# Dashboard_rev1.net
KiCad netlist of a schematic drawn in EAGLE
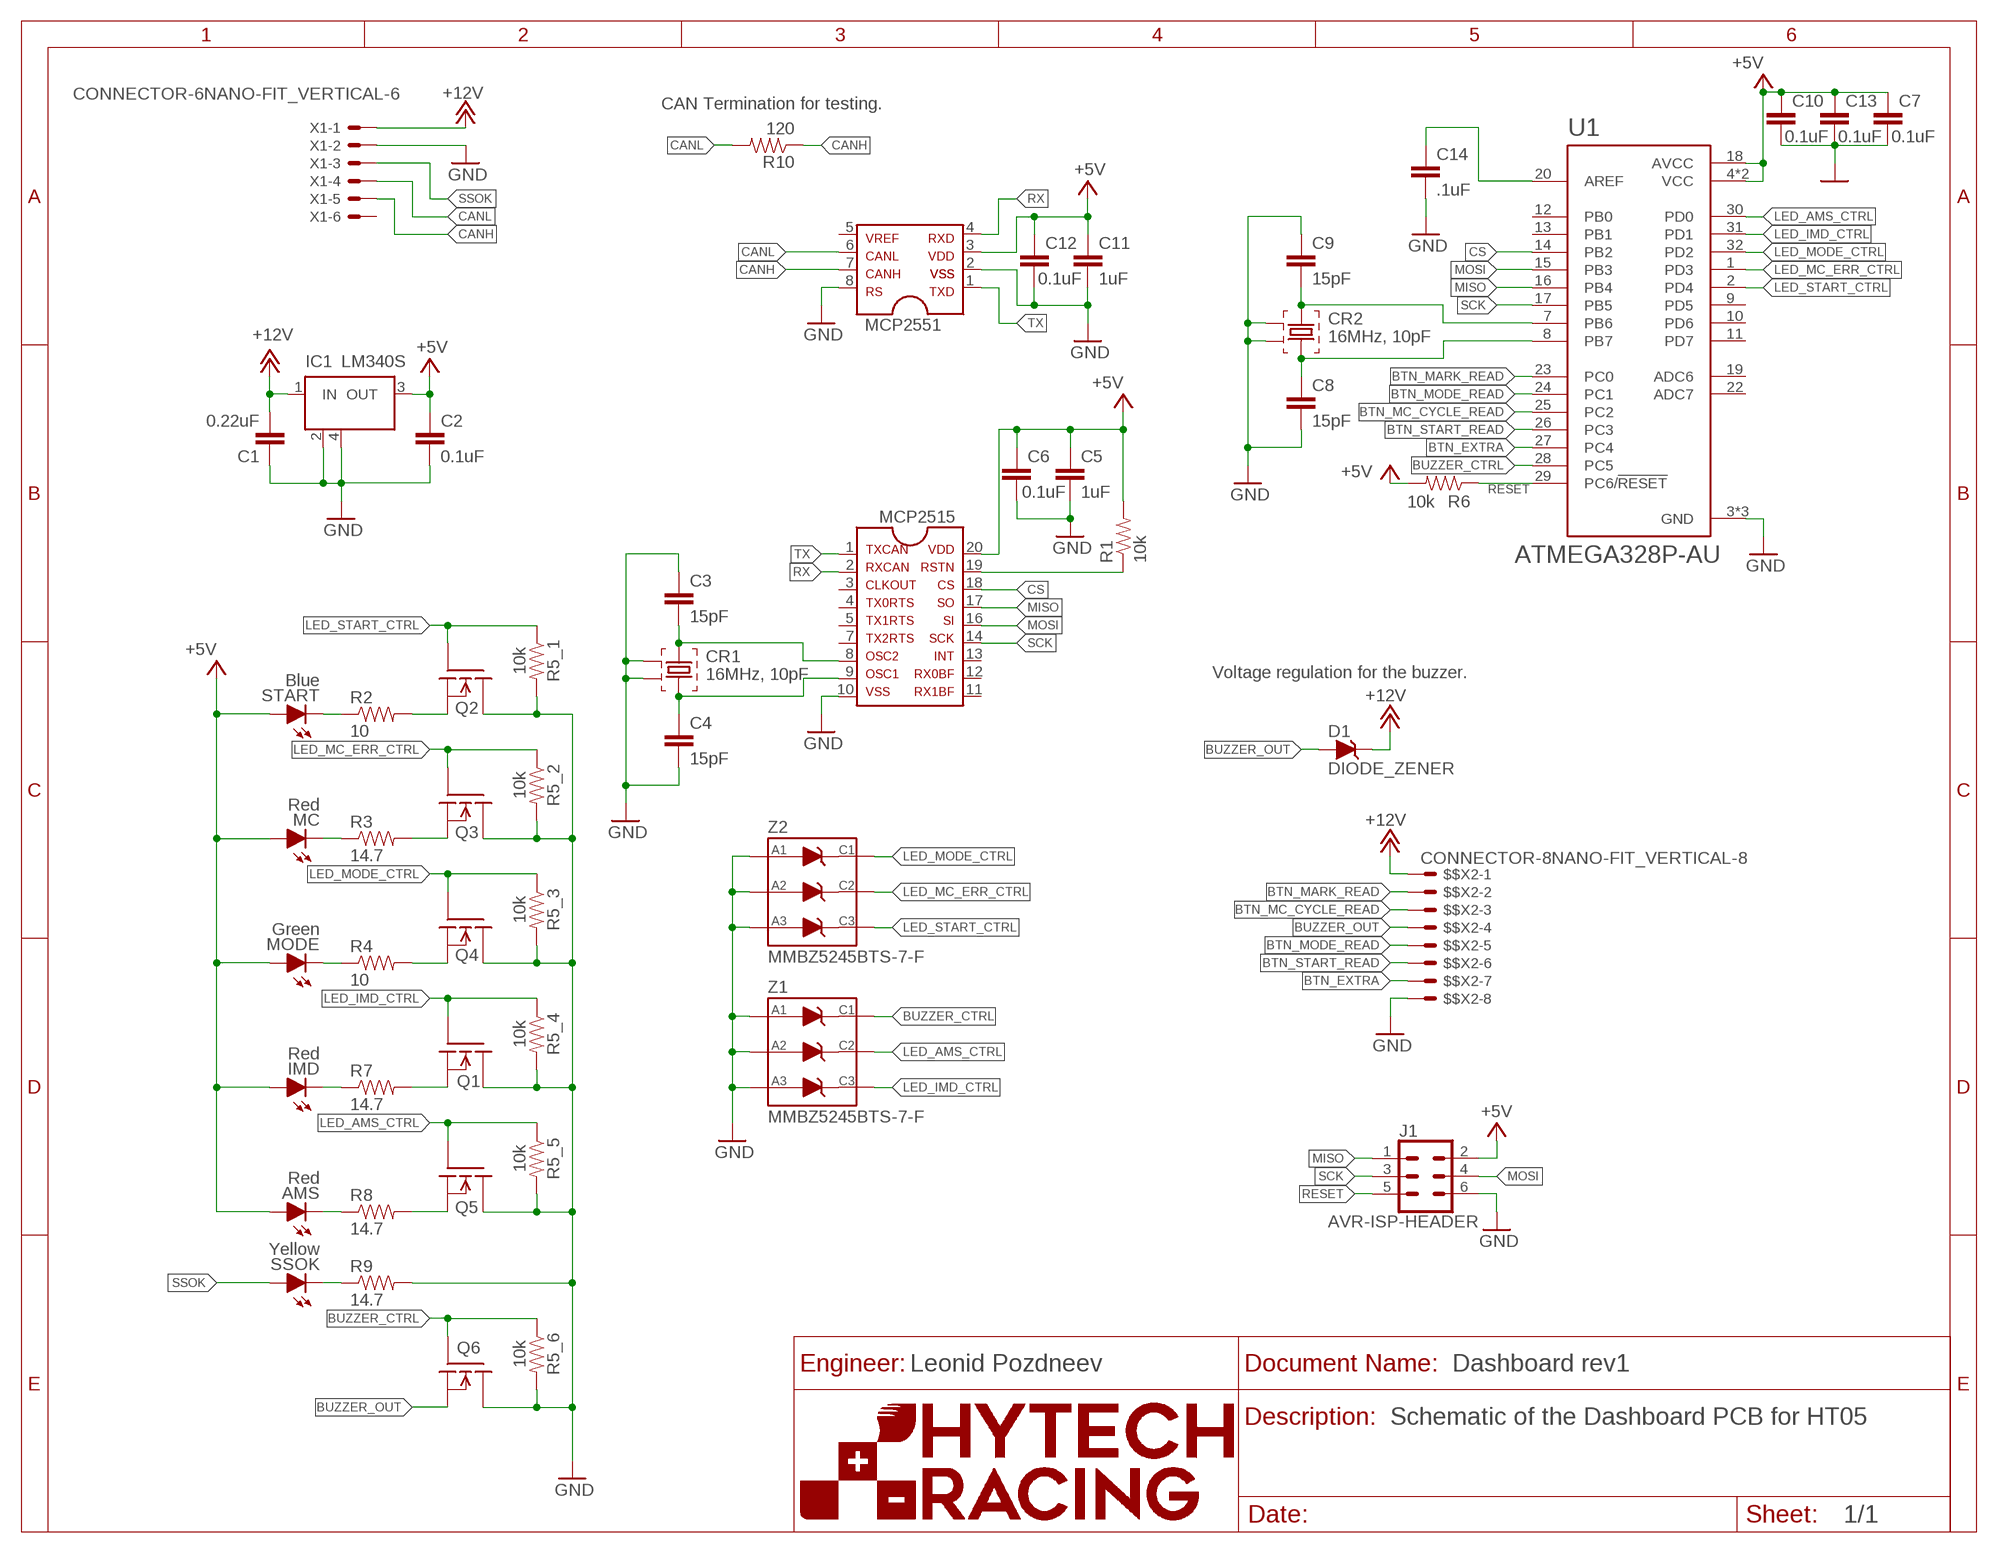
[diagram p0: schematic, sheet 1]

(export (version "E")
  (design (tool "Eeschema 10.0.6"))
  (components
    (comp (ref "$$X2")
      (value "CONNECTOR-8NANO-FIT_VERTICAL-8")
      (footprint "eagle-import:NANO-FIT_VERTICAL-8")
      (libsource (lib "eagle-import") (part "CONNECTOR-8NANO-FIT_VERTICAL-8"))
    )
    (comp (ref "AMS")
      (value "Red")
      (footprint "eagle-import:CREE_XP-E2")
      (libsource (lib "eagle-import") (part "LED"))
    )
    (comp (ref "C1")
      (value "0.22uF")
      (footprint "eagle-import:0603-CAP")
      (libsource (lib "eagle-import") (part "CAP0603-CAP"))
    )
    (comp (ref "C2")
      (value "0.1uF")
      (footprint "eagle-import:0603-CAP")
      (libsource (lib "eagle-import") (part "CAP0603-CAP"))
    )
    (comp (ref "C3")
      (value "15pF")
      (footprint "eagle-import:0603-CAP")
      (libsource (lib "eagle-import") (part "CAP0603-CAP"))
    )
    (comp (ref "C4")
      (value "15pF")
      (footprint "eagle-import:0603-CAP")
      (libsource (lib "eagle-import") (part "CAP0603-CAP"))
    )
    (comp (ref "C5")
      (value "1uF")
      (footprint "eagle-import:0603-CAP")
      (libsource (lib "eagle-import") (part "CAP0603-CAP"))
    )
    (comp (ref "C6")
      (value "0.1uF")
      (footprint "eagle-import:0603-CAP")
      (libsource (lib "eagle-import") (part "CAP0603-CAP"))
    )
    (comp (ref "C7")
      (value "0.1uF")
      (footprint "eagle-import:0603-CAP")
      (libsource (lib "eagle-import") (part "CAP0603-CAP"))
    )
    (comp (ref "C8")
      (value "15pF")
      (footprint "eagle-import:0603-CAP")
      (libsource (lib "eagle-import") (part "CAP0603-CAP"))
    )
    (comp (ref "C9")
      (value "15pF")
      (footprint "eagle-import:0603-CAP")
      (libsource (lib "eagle-import") (part "CAP0603-CAP"))
    )
    (comp (ref "C10")
      (value "0.1uF")
      (footprint "eagle-import:0603-CAP")
      (libsource (lib "eagle-import") (part "CAP0603-CAP"))
    )
    (comp (ref "C11")
      (value "1uF")
      (footprint "eagle-import:0603-CAP")
      (libsource (lib "eagle-import") (part "CAP0603-CAP"))
    )
    (comp (ref "C12")
      (value "0.1uF")
      (footprint "eagle-import:0603-CAP")
      (libsource (lib "eagle-import") (part "CAP0603-CAP"))
    )
    (comp (ref "C13")
      (value "0.1uF")
      (footprint "eagle-import:0603-CAP")
      (libsource (lib "eagle-import") (part "CAP0603-CAP"))
    )
    (comp (ref "C14")
      (value ".1uF")
      (footprint "eagle-import:0603-CAP")
      (libsource (lib "eagle-import") (part "CAP0603-CAP"))
    )
    (comp (ref "CR1")
      (value "16MHz, 10pF")
      (footprint "eagle-import:ABM3B")
      (libsource (lib "eagle-import") (part "ABM3B"))
    )
    (comp (ref "CR2")
      (value "16MHz, 10pF")
      (footprint "eagle-import:ABM3B")
      (libsource (lib "eagle-import") (part "ABM3B"))
    )
    (comp (ref "D1")
      (value "DIODE_ZENER")
      (footprint "eagle-import:SOT23")
      (libsource (lib "eagle-import") (part "DIODE_ZENER"))
    )
    (comp (ref "IC1")
      (value "LM340S")
      (footprint "eagle-import:SOT223")
      (libsource (lib "eagle-import") (part "LM340S"))
    )
    (comp (ref "IMD")
      (value "Red")
      (footprint "eagle-import:CREE_XP-E2")
      (libsource (lib "eagle-import") (part "LED"))
    )
    (comp (ref "J1")
      (value "AVR-ISP-HEADER")
      (footprint "eagle-import:2X03")
      (libsource (lib "eagle-import") (part "AVR-ISP-HEADER"))
    )
    (comp (ref "MC")
      (value "Red")
      (footprint "eagle-import:CREE_XP-E2")
      (libsource (lib "eagle-import") (part "LED"))
    )
    (comp (ref "MCP2515")
      (value "MCP2515TSSOP")
      (footprint "eagle-import:TSSOP-20")
      (libsource (lib "eagle-import") (part "MCP2515TSSOP"))
    )
    (comp (ref "MCP2551")
      (value "MCP2551")
      (footprint "eagle-import:SOIC-08")
      (libsource (lib "eagle-import") (part "MCP2551"))
    )
    (comp (ref "MODE")
      (value "Green")
      (footprint "eagle-import:CREE_XP-E2")
      (libsource (lib "eagle-import") (part "LED"))
    )
    (comp (ref "Q1")
      (value "DMG3406LSOT")
      (footprint "eagle-import:SOT23")
      (libsource (lib "eagle-import") (part "DMG3406LSOT"))
    )
    (comp (ref "Q2")
      (value "DMG3406LSOT")
      (footprint "eagle-import:SOT23")
      (libsource (lib "eagle-import") (part "DMG3406LSOT"))
    )
    (comp (ref "Q3")
      (value "DMG3406LSOT")
      (footprint "eagle-import:SOT23")
      (libsource (lib "eagle-import") (part "DMG3406LSOT"))
    )
    (comp (ref "Q4")
      (value "DMG3406LSOT")
      (footprint "eagle-import:SOT23")
      (libsource (lib "eagle-import") (part "DMG3406LSOT"))
    )
    (comp (ref "Q5")
      (value "DMG3406LSOT")
      (footprint "eagle-import:SOT23")
      (libsource (lib "eagle-import") (part "DMG3406LSOT"))
    )
    (comp (ref "Q6")
      (value "DMG3406LSOT")
      (footprint "eagle-import:SOT23")
      (libsource (lib "eagle-import") (part "DMG3406LSOT"))
    )
    (comp (ref "R1")
      (value "10k")
      (footprint "eagle-import:0603-RES")
      (libsource (lib "eagle-import") (part "RESISTOR0603"))
    )
    (comp (ref "R2")
      (value "10")
      (footprint "eagle-import:0603-RES")
      (libsource (lib "eagle-import") (part "RESISTOR0603"))
    )
    (comp (ref "R3")
      (value "14.7")
      (footprint "eagle-import:0603-RES")
      (libsource (lib "eagle-import") (part "RESISTOR0603"))
    )
    (comp (ref "R4")
      (value "10")
      (footprint "eagle-import:0603-RES")
      (libsource (lib "eagle-import") (part "RESISTOR0603"))
    )
    (comp (ref "R5")
      (value "10k")
      (footprint "eagle-import:CAT16-_8")
      (libsource (lib "eagle-import") (part "CAT16-8_1%F"))
    )
    (comp (ref "R6")
      (value "10k")
      (footprint "eagle-import:0603-RES")
      (libsource (lib "eagle-import") (part "RESISTOR0603"))
    )
    (comp (ref "R7")
      (value "14.7")
      (footprint "eagle-import:0603-RES")
      (libsource (lib "eagle-import") (part "RESISTOR0603"))
    )
    (comp (ref "R8")
      (value "14.7")
      (footprint "eagle-import:0603-RES")
      (libsource (lib "eagle-import") (part "RESISTOR0603"))
    )
    (comp (ref "R9")
      (value "14.7")
      (footprint "eagle-import:0603-RES")
      (libsource (lib "eagle-import") (part "RESISTOR0603"))
    )
    (comp (ref "R10")
      (value "120")
      (footprint "eagle-import:0603-RES")
      (libsource (lib "eagle-import") (part "RESISTOR0603-RES"))
    )
    (comp (ref "SSOK")
      (value "Yellow")
      (footprint "eagle-import:CREE_XP-E2")
      (libsource (lib "eagle-import") (part "LED"))
    )
    (comp (ref "START")
      (value "Blue")
      (footprint "eagle-import:CREE_XP-E2")
      (libsource (lib "eagle-import") (part "LED"))
    )
    (comp (ref "U1")
      (value "ATMEGA328P-AU")
      (footprint "eagle-import:QFP80P900X900X120-32N")
      (fields (field (name "MF") "Microchip"))
      (libsource (lib "eagle-import") (part "ATMEGA328P-AU"))
    )
    (comp (ref "X1")
      (value "CONNECTOR-6NANO-FIT_VERTICAL-6")
      (footprint "eagle-import:NANO-FIT_VERTICAL-6")
      (libsource (lib "eagle-import") (part "CONNECTOR-6NANO-FIT_VERTICAL-6"))
    )
    (comp (ref "Z1")
      (value "MMBZ5245BTS-7-F")
      (footprint "eagle-import:SOT363")
      (libsource (lib "eagle-import") (part "MMBZ5245BTS-7-F"))
    )
    (comp (ref "Z2")
      (value "MMBZ5245BTS-7-F")
      (footprint "eagle-import:SOT363")
      (libsource (lib "eagle-import") (part "MMBZ5245BTS-7-F"))
    )
  )
  (nets
    (net (code "1") (name "+5V") (class "Default")
      (node (ref "AMS") (pin "P$1") (pinfunction "A_P$1") (pintype "passive"))
      (node (ref "C10") (pin "1") (pinfunction "1_1") (pintype "passive"))
      (node (ref "C11") (pin "1") (pinfunction "1_1") (pintype "passive"))
      (node (ref "C12") (pin "1") (pinfunction "1_1") (pintype "passive"))
      (node (ref "C13") (pin "1") (pinfunction "1_1") (pintype "passive"))
      (node (ref "C2") (pin "1") (pinfunction "1_1") (pintype "passive"))
      (node (ref "C5") (pin "1") (pinfunction "1_1") (pintype "passive"))
      (node (ref "C6") (pin "1") (pinfunction "1_1") (pintype "passive"))
      (node (ref "C7") (pin "1") (pinfunction "1_1") (pintype "passive"))
      (node (ref "IC1") (pin "3") (pinfunction "OUT_3") (pintype "passive"))
      (node (ref "IMD") (pin "P$1") (pinfunction "A_P$1") (pintype "passive"))
      (node (ref "J1") (pin "2") (pinfunction "2_2") (pintype "passive"))
      (node (ref "MC") (pin "P$1") (pinfunction "A_P$1") (pintype "passive"))
      (node (ref "MCP2515") (pin "20") (pinfunction "VDD_20") (pintype "passive"))
      (node (ref "MCP2551") (pin "3") (pinfunction "3_3") (pintype "passive"))
      (node (ref "MODE") (pin "P$1") (pinfunction "A_P$1") (pintype "passive"))
      (node (ref "R1") (pin "2") (pinfunction "2_2") (pintype "passive"))
      (node (ref "R6") (pin "2") (pinfunction "2_2") (pintype "passive"))
      (node (ref "START") (pin "P$1") (pinfunction "A_P$1") (pintype "passive"))
      (node (ref "U1") (pin "18") (pinfunction "AVCC_18") (pintype "power_in"))
      (node (ref "U1") (pin "4") (pinfunction "VCC_4") (pintype "power_in"))
      (node (ref "U1") (pin "6") (pinfunction "VCC_6") (pintype "power_in"))
    )
    (net (code "2") (name "+12V") (class "Default")
      (node (ref "$$X2") (pin "P$1") (pinfunction "S_P$1") (pintype "passive"))
      (node (ref "C1") (pin "2") (pinfunction "2_2") (pintype "passive"))
      (node (ref "D1") (pin "3") (pinfunction "C_3") (pintype "passive"))
      (node (ref "IC1") (pin "1") (pinfunction "IN_1") (pintype "input"))
      (node (ref "X1") (pin "P$1") (pinfunction "S_P$1") (pintype "passive"))
    )
    (net (code "3") (name "BTN_EXTRA") (class "Default")
      (node (ref "$$X2") (pin "P$7") (pinfunction "S_P$7") (pintype "passive"))
      (node (ref "U1") (pin "27") (pinfunction "PC4_27") (pintype "bidirectional"))
    )
    (net (code "4") (name "BTN_MARK_READ") (class "Default")
      (node (ref "$$X2") (pin "P$2") (pinfunction "S_P$2") (pintype "passive"))
      (node (ref "U1") (pin "23") (pinfunction "PC0_23") (pintype "bidirectional"))
    )
    (net (code "5") (name "BTN_MC_CYCLE_READ") (class "Default")
      (node (ref "$$X2") (pin "P$3") (pinfunction "S_P$3") (pintype "passive"))
      (node (ref "U1") (pin "25") (pinfunction "PC2_25") (pintype "bidirectional"))
    )
    (net (code "6") (name "BTN_MODE_READ") (class "Default")
      (node (ref "$$X2") (pin "P$5") (pinfunction "S_P$5") (pintype "passive"))
      (node (ref "U1") (pin "24") (pinfunction "PC1_24") (pintype "bidirectional"))
    )
    (net (code "7") (name "BTN_START_READ") (class "Default")
      (node (ref "$$X2") (pin "P$6") (pinfunction "S_P$6") (pintype "passive"))
      (node (ref "U1") (pin "26") (pinfunction "PC3_26") (pintype "bidirectional"))
    )
    (net (code "8") (name "BUZZER_CTRL") (class "Default")
      (node (ref "Q6") (pin "1") (pinfunction "G_1") (pintype "passive"))
      (node (ref "R5") (pin "P$6") (pinfunction "1_P$6") (pintype "passive"))
      (node (ref "U1") (pin "28") (pinfunction "PC5_28") (pintype "bidirectional"))
      (node (ref "Z1") (pin "P$4") (pinfunction "C1_P$4") (pintype "bidirectional"))
    )
    (net (code "9") (name "BUZZER_OUT") (class "Default")
      (node (ref "$$X2") (pin "P$4") (pinfunction "S_P$4") (pintype "passive"))
      (node (ref "D1") (pin "1") (pinfunction "A_1") (pintype "passive"))
      (node (ref "Q6") (pin "2") (pinfunction "S_2") (pintype "passive"))
    )
    (net (code "10") (name "CANH") (class "Default")
      (node (ref "MCP2551") (pin "7") (pinfunction "7_7") (pintype "passive"))
      (node (ref "R10") (pin "1") (pinfunction "1_1") (pintype "passive"))
      (node (ref "X1") (pin "P$5") (pinfunction "S_P$5") (pintype "passive"))
    )
    (net (code "11") (name "CANL") (class "Default")
      (node (ref "MCP2551") (pin "6") (pinfunction "6_6") (pintype "passive"))
      (node (ref "R10") (pin "2") (pinfunction "2_2") (pintype "passive"))
      (node (ref "X1") (pin "P$4") (pinfunction "S_P$4") (pintype "passive"))
    )
    (net (code "12") (name "CS") (class "Default")
      (node (ref "MCP2515") (pin "18") (pinfunction "CS_18") (pintype "passive"))
      (node (ref "U1") (pin "14") (pinfunction "PB2_14") (pintype "bidirectional"))
    )
    (net (code "13") (name "GND") (class "Default")
      (node (ref "$$X2") (pin "P$8") (pinfunction "S_P$8") (pintype "passive"))
      (node (ref "C1") (pin "1") (pinfunction "1_1") (pintype "passive"))
      (node (ref "C10") (pin "2") (pinfunction "2_2") (pintype "passive"))
      (node (ref "C11") (pin "2") (pinfunction "2_2") (pintype "passive"))
      (node (ref "C12") (pin "2") (pinfunction "2_2") (pintype "passive"))
      (node (ref "C13") (pin "2") (pinfunction "2_2") (pintype "passive"))
      (node (ref "C14") (pin "2") (pinfunction "2_2") (pintype "passive"))
      (node (ref "C2") (pin "2") (pinfunction "2_2") (pintype "passive"))
      (node (ref "C3") (pin "1") (pinfunction "1_1") (pintype "passive"))
      (node (ref "C4") (pin "2") (pinfunction "2_2") (pintype "passive"))
      (node (ref "C5") (pin "2") (pinfunction "2_2") (pintype "passive"))
      (node (ref "C6") (pin "2") (pinfunction "2_2") (pintype "passive"))
      (node (ref "C7") (pin "2") (pinfunction "2_2") (pintype "passive"))
      (node (ref "C8") (pin "2") (pinfunction "2_2") (pintype "passive"))
      (node (ref "C9") (pin "1") (pinfunction "1_1") (pintype "passive"))
      (node (ref "CR1") (pin "P$2") (pinfunction "2_P$2") (pintype "passive"))
      (node (ref "CR1") (pin "P$4") (pinfunction "4_P$4") (pintype "passive"))
      (node (ref "CR2") (pin "P$2") (pinfunction "2_P$2") (pintype "passive"))
      (node (ref "CR2") (pin "P$4") (pinfunction "4_P$4") (pintype "passive"))
      (node (ref "IC1") (pin "2") (pinfunction "GND_2") (pintype "power_in"))
      (node (ref "IC1") (pin "4") (pinfunction "GND_4") (pintype "power_in"))
      (node (ref "J1") (pin "6") (pinfunction "6_6") (pintype "passive"))
      (node (ref "MCP2515") (pin "10") (pinfunction "VSS_10") (pintype "passive"))
      (node (ref "MCP2551") (pin "2") (pinfunction "2_2") (pintype "passive"))
      (node (ref "MCP2551") (pin "8") (pinfunction "8_8") (pintype "passive"))
      (node (ref "Q1") (pin "3") (pinfunction "D_3") (pintype "passive"))
      (node (ref "Q2") (pin "3") (pinfunction "D_3") (pintype "passive"))
      (node (ref "Q3") (pin "3") (pinfunction "D_3") (pintype "passive"))
      (node (ref "Q4") (pin "3") (pinfunction "D_3") (pintype "passive"))
      (node (ref "Q5") (pin "3") (pinfunction "D_3") (pintype "passive"))
      (node (ref "Q6") (pin "3") (pinfunction "D_3") (pintype "passive"))
      (node (ref "R5") (pin "P$11") (pinfunction "2_P$11") (pintype "passive"))
      (node (ref "R5") (pin "P$12") (pinfunction "2_P$12") (pintype "passive"))
      (node (ref "R5") (pin "P$13") (pinfunction "2_P$13") (pintype "passive"))
      (node (ref "R5") (pin "P$14") (pinfunction "2_P$14") (pintype "passive"))
      (node (ref "R5") (pin "P$15") (pinfunction "2_P$15") (pintype "passive"))
      (node (ref "R5") (pin "P$16") (pinfunction "2_P$16") (pintype "passive"))
      (node (ref "R9") (pin "2") (pinfunction "2_2") (pintype "passive"))
      (node (ref "U1") (pin "21") (pinfunction "GND_21") (pintype "power_in"))
      (node (ref "U1") (pin "3") (pinfunction "GND_3") (pintype "power_in"))
      (node (ref "U1") (pin "5") (pinfunction "GND_5") (pintype "power_in"))
      (node (ref "X1") (pin "P$2") (pinfunction "S_P$2") (pintype "passive"))
      (node (ref "Z1") (pin "P$1") (pinfunction "A1_P$1") (pintype "bidirectional"))
      (node (ref "Z1") (pin "P$2") (pinfunction "A2_P$2") (pintype "bidirectional"))
      (node (ref "Z1") (pin "P$3") (pinfunction "A3_P$3") (pintype "bidirectional"))
      (node (ref "Z2") (pin "P$1") (pinfunction "A1_P$1") (pintype "bidirectional"))
      (node (ref "Z2") (pin "P$2") (pinfunction "A2_P$2") (pintype "bidirectional"))
      (node (ref "Z2") (pin "P$3") (pinfunction "A3_P$3") (pintype "bidirectional"))
    )
    (net (code "14") (name "LED_AMS_CTRL") (class "Default")
      (node (ref "Q5") (pin "1") (pinfunction "G_1") (pintype "passive"))
      (node (ref "R5") (pin "P$5") (pinfunction "1_P$5") (pintype "passive"))
      (node (ref "U1") (pin "30") (pinfunction "PD0_30") (pintype "bidirectional"))
      (node (ref "Z1") (pin "P$5") (pinfunction "C2_P$5") (pintype "bidirectional"))
    )
    (net (code "15") (name "LED_IMD_CTRL") (class "Default")
      (node (ref "Q1") (pin "1") (pinfunction "G_1") (pintype "passive"))
      (node (ref "R5") (pin "P$4") (pinfunction "1_P$4") (pintype "passive"))
      (node (ref "U1") (pin "31") (pinfunction "PD1_31") (pintype "bidirectional"))
      (node (ref "Z1") (pin "P$6") (pinfunction "C3_P$6") (pintype "bidirectional"))
    )
    (net (code "16") (name "LED_MC_ERR_CTRL") (class "Default")
      (node (ref "Q3") (pin "1") (pinfunction "G_1") (pintype "passive"))
      (node (ref "R5") (pin "P$2") (pinfunction "1_P$2") (pintype "passive"))
      (node (ref "U1") (pin "1") (pinfunction "PD3_1") (pintype "bidirectional"))
      (node (ref "Z2") (pin "P$5") (pinfunction "C2_P$5") (pintype "bidirectional"))
    )
    (net (code "17") (name "LED_MODE_CTRL") (class "Default")
      (node (ref "Q4") (pin "1") (pinfunction "G_1") (pintype "passive"))
      (node (ref "R5") (pin "P$3") (pinfunction "1_P$3") (pintype "passive"))
      (node (ref "U1") (pin "32") (pinfunction "PD2_32") (pintype "bidirectional"))
      (node (ref "Z2") (pin "P$4") (pinfunction "C1_P$4") (pintype "bidirectional"))
    )
    (net (code "18") (name "LED_START_CTRL") (class "Default")
      (node (ref "Q2") (pin "1") (pinfunction "G_1") (pintype "passive"))
      (node (ref "R5") (pin "P$1") (pinfunction "1_P$1") (pintype "passive"))
      (node (ref "U1") (pin "2") (pinfunction "PD4_2") (pintype "bidirectional"))
      (node (ref "Z2") (pin "P$6") (pinfunction "C3_P$6") (pintype "bidirectional"))
    )
    (net (code "19") (name "MISO") (class "Default")
      (node (ref "J1") (pin "1") (pinfunction "1_1") (pintype "passive"))
      (node (ref "MCP2515") (pin "17") (pinfunction "SO_17") (pintype "passive"))
      (node (ref "U1") (pin "16") (pinfunction "PB4_16") (pintype "bidirectional"))
    )
    (net (code "20") (name "MOSI") (class "Default")
      (node (ref "J1") (pin "4") (pinfunction "4_4") (pintype "passive"))
      (node (ref "MCP2515") (pin "16") (pinfunction "SI_16") (pintype "passive"))
      (node (ref "U1") (pin "15") (pinfunction "PB3_15") (pintype "bidirectional"))
    )
    (net (code "21") (name "Net-(AMS-C)") (class "Default")
      (node (ref "AMS") (pin "P$2") (pinfunction "C_P$2") (pintype "passive"))
      (node (ref "R8") (pin "1") (pinfunction "1_1") (pintype "passive"))
    )
    (net (code "22") (name "Net-(CR1-1)") (class "Default")
      (node (ref "C3") (pin "2") (pinfunction "2_2") (pintype "passive"))
      (node (ref "CR1") (pin "P$1") (pinfunction "1_P$1") (pintype "passive"))
      (node (ref "MCP2515") (pin "8") (pinfunction "OSC2_8") (pintype "passive"))
    )
    (net (code "23") (name "Net-(CR1-3)") (class "Default")
      (node (ref "C4") (pin "1") (pinfunction "1_1") (pintype "passive"))
      (node (ref "CR1") (pin "P$3") (pinfunction "3_P$3") (pintype "passive"))
      (node (ref "MCP2515") (pin "9") (pinfunction "OSC1_9") (pintype "passive"))
    )
    (net (code "24") (name "Net-(CR2-1)") (class "Default")
      (node (ref "C9") (pin "2") (pinfunction "2_2") (pintype "passive"))
      (node (ref "CR2") (pin "P$1") (pinfunction "1_P$1") (pintype "passive"))
      (node (ref "U1") (pin "7") (pinfunction "PB6_7") (pintype "bidirectional"))
    )
    (net (code "25") (name "Net-(CR2-3)") (class "Default")
      (node (ref "C8") (pin "1") (pinfunction "1_1") (pintype "passive"))
      (node (ref "CR2") (pin "P$3") (pinfunction "3_P$3") (pintype "passive"))
      (node (ref "U1") (pin "8") (pinfunction "PB7_8") (pintype "bidirectional"))
    )
    (net (code "26") (name "Net-(IMD-C)") (class "Default")
      (node (ref "IMD") (pin "P$2") (pinfunction "C_P$2") (pintype "passive"))
      (node (ref "R7") (pin "1") (pinfunction "1_1") (pintype "passive"))
    )
    (net (code "27") (name "Net-(MC-C)") (class "Default")
      (node (ref "MC") (pin "P$2") (pinfunction "C_P$2") (pintype "passive"))
      (node (ref "R3") (pin "1") (pinfunction "1_1") (pintype "passive"))
    )
    (net (code "28") (name "Net-(MCP2515-RSTN)") (class "Default")
      (node (ref "MCP2515") (pin "19") (pinfunction "RSTN_19") (pintype "passive"))
      (node (ref "R1") (pin "1") (pinfunction "1_1") (pintype "passive"))
    )
    (net (code "29") (name "Net-(MODE-C)") (class "Default")
      (node (ref "MODE") (pin "P$2") (pinfunction "C_P$2") (pintype "passive"))
      (node (ref "R4") (pin "1") (pinfunction "1_1") (pintype "passive"))
    )
    (net (code "30") (name "Net-(Q1-S)") (class "Default")
      (node (ref "Q1") (pin "2") (pinfunction "S_2") (pintype "passive"))
      (node (ref "R7") (pin "2") (pinfunction "2_2") (pintype "passive"))
    )
    (net (code "31") (name "Net-(Q2-S)") (class "Default")
      (node (ref "Q2") (pin "2") (pinfunction "S_2") (pintype "passive"))
      (node (ref "R2") (pin "2") (pinfunction "2_2") (pintype "passive"))
    )
    (net (code "32") (name "Net-(Q3-S)") (class "Default")
      (node (ref "Q3") (pin "2") (pinfunction "S_2") (pintype "passive"))
      (node (ref "R3") (pin "2") (pinfunction "2_2") (pintype "passive"))
    )
    (net (code "33") (name "Net-(Q4-S)") (class "Default")
      (node (ref "Q4") (pin "2") (pinfunction "S_2") (pintype "passive"))
      (node (ref "R4") (pin "2") (pinfunction "2_2") (pintype "passive"))
    )
    (net (code "34") (name "Net-(Q5-S)") (class "Default")
      (node (ref "Q5") (pin "2") (pinfunction "S_2") (pintype "passive"))
      (node (ref "R8") (pin "2") (pinfunction "2_2") (pintype "passive"))
    )
    (net (code "35") (name "Net-(SSOK-C)") (class "Default")
      (node (ref "R9") (pin "1") (pinfunction "1_1") (pintype "passive"))
      (node (ref "SSOK") (pin "P$2") (pinfunction "C_P$2") (pintype "passive"))
    )
    (net (code "36") (name "Net-(START-C)") (class "Default")
      (node (ref "R2") (pin "1") (pinfunction "1_1") (pintype "passive"))
      (node (ref "START") (pin "P$2") (pinfunction "C_P$2") (pintype "passive"))
    )
    (net (code "37") (name "Net-(U1-AREF)") (class "Default")
      (node (ref "C14") (pin "1") (pinfunction "1_1") (pintype "passive"))
      (node (ref "U1") (pin "20") (pinfunction "AREF_20") (pintype "input"))
    )
    (net (code "38") (name "RESET") (class "Default")
      (node (ref "J1") (pin "5") (pinfunction "5_5") (pintype "passive"))
      (node (ref "R6") (pin "1") (pinfunction "1_1") (pintype "passive"))
      (node (ref "U1") (pin "29") (pinfunction "PC6/~{RESET}_29") (pintype "bidirectional"))
    )
    (net (code "39") (name "RX") (class "Default")
      (node (ref "MCP2515") (pin "2") (pinfunction "RXCAN_2") (pintype "passive"))
      (node (ref "MCP2551") (pin "4") (pinfunction "4_4") (pintype "passive"))
    )
    (net (code "40") (name "SCK") (class "Default")
      (node (ref "J1") (pin "3") (pinfunction "3_3") (pintype "passive"))
      (node (ref "MCP2515") (pin "14") (pinfunction "SCK_14") (pintype "passive"))
      (node (ref "U1") (pin "17") (pinfunction "PB5_17") (pintype "bidirectional"))
    )
    (net (code "41") (name "SSOK") (class "Default")
      (node (ref "SSOK") (pin "P$1") (pinfunction "A_P$1") (pintype "passive"))
      (node (ref "X1") (pin "P$3") (pinfunction "S_P$3") (pintype "passive"))
    )
    (net (code "42") (name "TX") (class "Default")
      (node (ref "MCP2515") (pin "1") (pinfunction "TXCAN_1") (pintype "passive"))
      (node (ref "MCP2551") (pin "1") (pinfunction "1_1") (pintype "passive"))
    )
    (net (code "43") (name "unconnected-(MCP2515-CLKOUT-Pad3)") (class "Default")
      (node (ref "MCP2515") (pin "3") (pinfunction "CLKOUT_3") (pintype "passive"))
    )
    (net (code "44") (name "unconnected-(MCP2515-INT-Pad13)") (class "Default")
      (node (ref "MCP2515") (pin "13") (pinfunction "INT_13") (pintype "passive"))
    )
    (net (code "45") (name "unconnected-(MCP2515-RX0BF-Pad12)") (class "Default")
      (node (ref "MCP2515") (pin "12") (pinfunction "RX0BF_12") (pintype "passive"))
    )
    (net (code "46") (name "unconnected-(MCP2515-RX1BF-Pad11)") (class "Default")
      (node (ref "MCP2515") (pin "11") (pinfunction "RX1BF_11") (pintype "passive"))
    )
    (net (code "47") (name "unconnected-(MCP2515-TX0RTS-Pad4)") (class "Default")
      (node (ref "MCP2515") (pin "4") (pinfunction "TX0RTS_4") (pintype "passive"))
    )
    (net (code "48") (name "unconnected-(MCP2515-TX1RTS-Pad5)") (class "Default")
      (node (ref "MCP2515") (pin "5") (pinfunction "TX1RTS_5") (pintype "passive"))
    )
    (net (code "49") (name "unconnected-(MCP2515-TX2RTS-Pad7)") (class "Default")
      (node (ref "MCP2515") (pin "7") (pinfunction "TX2RTS_7") (pintype "passive"))
    )
    (net (code "50") (name "unconnected-(MCP2551-Pad5)") (class "Default")
      (node (ref "MCP2551") (pin "5") (pinfunction "5_5") (pintype "passive"))
    )
    (net (code "51") (name "unconnected-(U1-ADC6-Pad19)") (class "Default")
      (node (ref "U1") (pin "19") (pinfunction "ADC6_19") (pintype "bidirectional"))
    )
    (net (code "52") (name "unconnected-(U1-ADC7-Pad22)") (class "Default")
      (node (ref "U1") (pin "22") (pinfunction "ADC7_22") (pintype "bidirectional"))
    )
    (net (code "53") (name "unconnected-(U1-PB0-Pad12)") (class "Default")
      (node (ref "U1") (pin "12") (pinfunction "PB0_12") (pintype "bidirectional"))
    )
    (net (code "54") (name "unconnected-(U1-PB1-Pad13)") (class "Default")
      (node (ref "U1") (pin "13") (pinfunction "PB1_13") (pintype "bidirectional"))
    )
    (net (code "55") (name "unconnected-(U1-PD5-Pad9)") (class "Default")
      (node (ref "U1") (pin "9") (pinfunction "PD5_9") (pintype "bidirectional"))
    )
    (net (code "56") (name "unconnected-(U1-PD6-Pad10)") (class "Default")
      (node (ref "U1") (pin "10") (pinfunction "PD6_10") (pintype "bidirectional"))
    )
    (net (code "57") (name "unconnected-(U1-PD7-Pad11)") (class "Default")
      (node (ref "U1") (pin "11") (pinfunction "PD7_11") (pintype "bidirectional"))
    )
    (net (code "58") (name "unconnected-(X1F-S-PadP$6)") (class "Default")
      (node (ref "X1") (pin "P$6") (pinfunction "S_P$6") (pintype "passive"))
    )
  )
)
